# PowerSupply1.net
KiCad netlist of a schematic drawn in Altium Designer
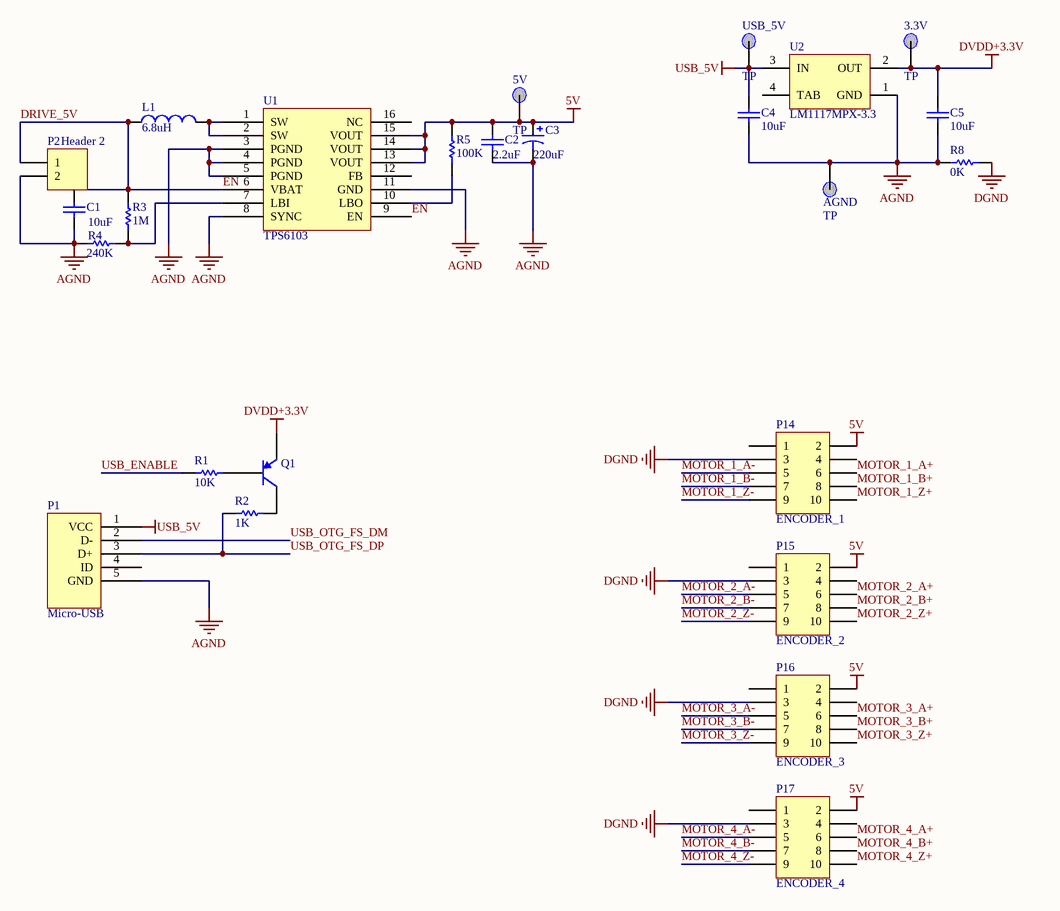
[diagram p0: PowerSupply1.SchDoc]

(export (version "E")
  (design (tool "Eeschema 10.0.6"))
  (components
    (comp (ref "3.3V") (value "TP") (footprint "TestPort") (libsource (lib "CTs_FYF") (part "TestPoint")))
    (comp (ref "5V") (value "TP") (footprint "TestPort") (libsource (lib "CTs_FYF") (part "TestPoint")))
    (comp (ref "AGND") (value "TP") (footprint "TestPort") (libsource (lib "") (part "TestPoint_1")))
    (comp (ref "C1")
      (value "10uF")
      (footprint "1608[0603]")
      (description "Capacitor")
      (fields (field (name "PUBLISHER") "Altium Limited"))
      (libsource (lib "Miscellaneous Devices") (part "Cap"))
    )
    (comp (ref "C2")
      (value "2.2uF")
      (footprint "1608[0603]")
      (description "Capacitor")
      (fields (field (name "PUBLISHER") "Altium Limited"))
      (libsource (lib "Miscellaneous Devices") (part "Cap"))
    )
    (comp (ref "C3")
      (value "220uF")
      (footprint "6TPF220M5L")
      (description "Polarized Capacitor (Radial)")
      (fields (field (name "PUBLISHER") "Altium Limited"))
      (libsource (lib "Miscellaneous Devices") (part "Cap Pol1"))
    )
    (comp (ref "C4")
      (value "10uF")
      (footprint "1608[0603]")
      (description "Capacitor")
      (fields (field (name "PUBLISHER") "Altium Limited"))
      (libsource (lib "Miscellaneous Devices") (part "Cap"))
    )
    (comp (ref "C5")
      (value "10uF")
      (footprint "1608[0603]")
      (description "Capacitor")
      (fields (field (name "PUBLISHER") "Altium Limited"))
      (libsource (lib "Miscellaneous Devices") (part "Cap"))
    )
    (comp (ref "L1")
      (value "6.8uH")
      (footprint "B82464G4682M")
      (description "Inductor")
      (fields (field (name "PUBLISHER") "Altium Limited"))
      (libsource (lib "Miscellaneous Devices") (part "Inductor"))
    )
    (comp (ref "P1")
      (value "Micro-USB")
      (footprint "Micro-USB")
      (libsource (lib "CTs_FYF") (part "Micro-USB"))
    )
    (comp (ref "P2")
      (value "Header 2")
      (footprint "HDR1X2")
      (description "Header, 2-Pin")
      (fields (field (name "PUBLISHER") "Altium Limited"))
      (libsource (lib "Miscellaneous Connectors") (part "Header 2"))
    )
    (comp (ref "P14")
      (value "ENCODER_1")
      (footprint "MHDR2X5")
      (description "Header, 5-Pin, Dual row")
      (fields (field (name "PUBLISHER") "Altium Limited"))
      (libsource (lib "Miscellaneous Connectors") (part "Header 5X2"))
    )
    (comp (ref "P15")
      (value "ENCODER_2")
      (footprint "MHDR2X5")
      (description "Header, 5-Pin, Dual row")
      (fields (field (name "PUBLISHER") "Altium Limited"))
      (libsource (lib "Miscellaneous Connectors") (part "Header 5X2"))
    )
    (comp (ref "P16")
      (value "ENCODER_3")
      (footprint "MHDR2X5")
      (description "Header, 5-Pin, Dual row")
      (fields (field (name "PUBLISHER") "Altium Limited"))
      (libsource (lib "Miscellaneous Connectors") (part "Header 5X2"))
    )
    (comp (ref "P17")
      (value "ENCODER_4")
      (footprint "MHDR2X5")
      (description "Header, 5-Pin, Dual row")
      (fields (field (name "PUBLISHER") "Altium Limited"))
      (libsource (lib "Miscellaneous Connectors") (part "Header 5X2"))
    )
    (comp (ref "Q1")
      (value "PNP")
      (footprint "SOT-23B_N")
      (description "PNP Bipolar Transistor")
      (fields (field (name "PUBLISHER") "Altium Limited"))
      (libsource (lib "Miscellaneous Devices") (part "PNP"))
    )
    (comp (ref "R1")
      (value "10K")
      (footprint "J1-0603")
      (description "Resistor")
      (fields (field (name "PUBLISHER") "Altium Limited"))
      (libsource (lib "Miscellaneous Devices") (part "Res1"))
    )
    (comp (ref "R2")
      (value "1K")
      (footprint "RES[0402]")
      (description "Resistor")
      (fields (field (name "PUBLISHER") "Altium Limited"))
      (libsource (lib "Miscellaneous Devices") (part "Res1"))
    )
    (comp (ref "R3")
      (value "1M")
      (footprint "J1-0603")
      (description "Resistor")
      (fields (field (name "PUBLISHER") "Altium Limited"))
      (libsource (lib "Miscellaneous Devices") (part "Res1"))
    )
    (comp (ref "R4")
      (value "240K")
      (footprint "J1-0603")
      (description "Resistor")
      (fields (field (name "PUBLISHER") "Altium Limited"))
      (libsource (lib "Miscellaneous Devices") (part "Res1"))
    )
    (comp (ref "R5")
      (value "100K")
      (footprint "J1-0603")
      (description "Resistor")
      (fields (field (name "PUBLISHER") "Altium Limited"))
      (libsource (lib "Miscellaneous Devices") (part "Res1"))
    )
    (comp (ref "R8")
      (value "0K")
      (footprint "J1-0603")
      (description "Resistor")
      (fields (field (name "PUBLISHER") "Altium Limited"))
      (libsource (lib "Miscellaneous Devices") (part "Res1"))
    )
    (comp (ref "U1") (value "TPS6103") (footprint "TI_PWP_G16") (libsource (lib "CTs_FYF") (part "TPS6103")))
    (comp (ref "U2")
      (value "LM1117MPX-3.3")
      (footprint "SOT230-4N")
      (description "800mA Low-Dropout Linear Regulator, 4-pin SOT-223")
      (fields
        (field (name "MANUFACTURER") "National Semiconductor")
        (field (name "PUBLISHER") "Altium Limited")
      )
      (libsource (lib "NSC LDO") (part "LM1117MPX-3.3"))
    )
    (comp (ref "USB_5V") (value "TP") (footprint "TestPort") (libsource (lib "CTs_FYF") (part "TestPoint")))
  )
  (nets
    (net (code "1") (name "/DRIVE_5V") (class "Default")
      (node (ref "C1") (pin "2") (pinfunction "2_2") (pintype "passive"))
      (node (ref "L1") (pin "1") (pinfunction "1_1") (pintype "passive"))
      (node (ref "P2") (pin "1") (pinfunction "1_1") (pintype "passive"))
      (node (ref "R3") (pin "2") (pinfunction "2_2") (pintype "passive"))
      (node (ref "U1") (pin "6") (pinfunction "VBAT_6") (pintype "passive"))
      (node (ref "U1") (pin "9") (pinfunction "EN_9") (pintype "passive"))
    )
    (net (code "2") (name "/MOTOR_1_A+") (class "Default")
      (node (ref "P14") (pin "6") (pinfunction "6_6") (pintype "passive"))
    )
    (net (code "3") (name "/MOTOR_1_A-") (class "Default")
      (node (ref "P14") (pin "5") (pinfunction "5_5") (pintype "passive"))
    )
    (net (code "4") (name "/MOTOR_1_B+") (class "Default")
      (node (ref "P14") (pin "8") (pinfunction "8_8") (pintype "passive"))
    )
    (net (code "5") (name "/MOTOR_1_B-") (class "Default")
      (node (ref "P14") (pin "7") (pinfunction "7_7") (pintype "passive"))
    )
    (net (code "6") (name "/MOTOR_1_Z+") (class "Default")
      (node (ref "P14") (pin "10") (pinfunction "10_10") (pintype "passive"))
    )
    (net (code "7") (name "/MOTOR_1_Z-") (class "Default")
      (node (ref "P14") (pin "9") (pinfunction "9_9") (pintype "passive"))
    )
    (net (code "8") (name "/MOTOR_2_A+") (class "Default")
      (node (ref "P15") (pin "6") (pinfunction "6_6") (pintype "passive"))
    )
    (net (code "9") (name "/MOTOR_2_A-") (class "Default")
      (node (ref "P15") (pin "5") (pinfunction "5_5") (pintype "passive"))
    )
    (net (code "10") (name "/MOTOR_2_B+") (class "Default")
      (node (ref "P15") (pin "8") (pinfunction "8_8") (pintype "passive"))
    )
    (net (code "11") (name "/MOTOR_2_B-") (class "Default")
      (node (ref "P15") (pin "7") (pinfunction "7_7") (pintype "passive"))
    )
    (net (code "12") (name "/MOTOR_2_Z+") (class "Default")
      (node (ref "P15") (pin "10") (pinfunction "10_10") (pintype "passive"))
    )
    (net (code "13") (name "/MOTOR_2_Z-") (class "Default")
      (node (ref "P15") (pin "9") (pinfunction "9_9") (pintype "passive"))
    )
    (net (code "14") (name "/MOTOR_3_A+") (class "Default")
      (node (ref "P16") (pin "6") (pinfunction "6_6") (pintype "passive"))
    )
    (net (code "15") (name "/MOTOR_3_A-") (class "Default")
      (node (ref "P16") (pin "5") (pinfunction "5_5") (pintype "passive"))
    )
    (net (code "16") (name "/MOTOR_3_B+") (class "Default")
      (node (ref "P16") (pin "8") (pinfunction "8_8") (pintype "passive"))
    )
    (net (code "17") (name "/MOTOR_3_B-") (class "Default")
      (node (ref "P16") (pin "7") (pinfunction "7_7") (pintype "passive"))
    )
    (net (code "18") (name "/MOTOR_3_Z+") (class "Default")
      (node (ref "P16") (pin "10") (pinfunction "10_10") (pintype "passive"))
    )
    (net (code "19") (name "/MOTOR_3_Z-") (class "Default")
      (node (ref "P16") (pin "9") (pinfunction "9_9") (pintype "passive"))
    )
    (net (code "20") (name "/MOTOR_4_A+") (class "Default")
      (node (ref "P17") (pin "6") (pinfunction "6_6") (pintype "passive"))
    )
    (net (code "21") (name "/MOTOR_4_A-") (class "Default")
      (node (ref "P17") (pin "5") (pinfunction "5_5") (pintype "passive"))
    )
    (net (code "22") (name "/MOTOR_4_B+") (class "Default")
      (node (ref "P17") (pin "8") (pinfunction "8_8") (pintype "passive"))
    )
    (net (code "23") (name "/MOTOR_4_B-") (class "Default")
      (node (ref "P17") (pin "7") (pinfunction "7_7") (pintype "passive"))
    )
    (net (code "24") (name "/MOTOR_4_Z+") (class "Default")
      (node (ref "P17") (pin "10") (pinfunction "10_10") (pintype "passive"))
    )
    (net (code "25") (name "/MOTOR_4_Z-") (class "Default")
      (node (ref "P17") (pin "9") (pinfunction "9_9") (pintype "passive"))
    )
    (net (code "26") (name "/USB_ENABLE") (class "Default")
      (node (ref "R1") (pin "1") (pinfunction "1_1") (pintype "passive"))
    )
    (net (code "27") (name "/USB_OTG_FS_DM") (class "Default")
      (node (ref "P1") (pin "2") (pinfunction "D-_2") (pintype "passive"))
    )
    (net (code "28") (name "/USB_OTG_FS_DP") (class "Default")
      (node (ref "P1") (pin "3") (pinfunction "D+_3") (pintype "passive"))
      (node (ref "R2") (pin "2") (pinfunction "2_2") (pintype "passive"))
    )
    (net (code "29") (name "5V") (class "Default")
      (node (ref "5V") (pin "0") (pinfunction "0_0") (pintype "passive"))
      (node (ref "C2") (pin "2") (pinfunction "2_2") (pintype "passive"))
      (node (ref "C3") (pin "1") (pinfunction "1_1") (pintype "passive"))
      (node (ref "P14") (pin "2") (pinfunction "2_2") (pintype "passive"))
      (node (ref "P15") (pin "2") (pinfunction "2_2") (pintype "passive"))
      (node (ref "P16") (pin "2") (pinfunction "2_2") (pintype "passive"))
      (node (ref "P17") (pin "2") (pinfunction "2_2") (pintype "passive"))
      (node (ref "R5") (pin "2") (pinfunction "2_2") (pintype "passive"))
      (node (ref "U1") (pin "13") (pinfunction "VOUT_13") (pintype "passive"))
      (node (ref "U1") (pin "14") (pinfunction "VOUT_14") (pintype "passive"))
      (node (ref "U1") (pin "15") (pinfunction "VOUT_15") (pintype "passive"))
    )
    (net (code "30") (name "AGND") (class "Default")
      (node (ref "AGND") (pin "0") (pinfunction "0_0") (pintype "passive"))
      (node (ref "C1") (pin "1") (pinfunction "1_1") (pintype "passive"))
      (node (ref "C2") (pin "1") (pinfunction "1_1") (pintype "passive"))
      (node (ref "C3") (pin "2") (pinfunction "2_2") (pintype "passive"))
      (node (ref "C4") (pin "2") (pinfunction "2_2") (pintype "passive"))
      (node (ref "C5") (pin "2") (pinfunction "2_2") (pintype "passive"))
      (node (ref "P1") (pin "5") (pinfunction "GND_5") (pintype "passive"))
      (node (ref "P2") (pin "2") (pinfunction "2_2") (pintype "passive"))
      (node (ref "R4") (pin "1") (pinfunction "1_1") (pintype "passive"))
      (node (ref "R8") (pin "1") (pinfunction "1_1") (pintype "passive"))
      (node (ref "U1") (pin "11") (pinfunction "GND_11") (pintype "passive"))
      (node (ref "U1") (pin "3") (pinfunction "PGND_3") (pintype "passive"))
      (node (ref "U1") (pin "4") (pinfunction "PGND_4") (pintype "passive"))
      (node (ref "U1") (pin "5") (pinfunction "PGND_5") (pintype "passive"))
      (node (ref "U1") (pin "8") (pinfunction "SYNC_8") (pintype "passive"))
      (node (ref "U2") (pin "1") (pinfunction "GND_1") (pintype "power_in"))
    )
    (net (code "31") (name "DGND") (class "Default")
      (node (ref "P14") (pin "3") (pinfunction "3_3") (pintype "passive"))
      (node (ref "P15") (pin "3") (pinfunction "3_3") (pintype "passive"))
      (node (ref "P16") (pin "3") (pinfunction "3_3") (pintype "passive"))
      (node (ref "P17") (pin "3") (pinfunction "3_3") (pintype "passive"))
      (node (ref "R8") (pin "2") (pinfunction "2_2") (pintype "passive"))
    )
    (net (code "32") (name "DVDD+3.3V") (class "Default")
      (node (ref "3.3V") (pin "0") (pinfunction "0_0") (pintype "passive"))
      (node (ref "C5") (pin "1") (pinfunction "1_1") (pintype "passive"))
      (node (ref "Q1") (pin "3") (pinfunction "E_3") (pintype "passive"))
      (node (ref "U2") (pin "2") (pinfunction "OUT_2") (pintype "power_in"))
    )
    (net (code "33") (name "Net-(L1-Pad2)") (class "Default")
      (node (ref "L1") (pin "2") (pinfunction "2_2") (pintype "passive"))
      (node (ref "U1") (pin "1") (pinfunction "SW_1") (pintype "passive"))
      (node (ref "U1") (pin "2") (pinfunction "SW_2") (pintype "passive"))
    )
    (net (code "34") (name "Net-(Q1-B)") (class "Default")
      (node (ref "Q1") (pin "2") (pinfunction "B_2") (pintype "passive"))
      (node (ref "R1") (pin "2") (pinfunction "2_2") (pintype "passive"))
    )
    (net (code "35") (name "Net-(Q1-C)") (class "Default")
      (node (ref "Q1") (pin "1") (pinfunction "C_1") (pintype "passive"))
      (node (ref "R2") (pin "1") (pinfunction "1_1") (pintype "passive"))
    )
    (net (code "36") (name "Net-(U1-LBI)") (class "Default")
      (node (ref "R3") (pin "1") (pinfunction "1_1") (pintype "passive"))
      (node (ref "R4") (pin "2") (pinfunction "2_2") (pintype "passive"))
      (node (ref "U1") (pin "7") (pinfunction "LBI_7") (pintype "passive"))
    )
    (net (code "37") (name "Net-(U1-LBO)") (class "Default")
      (node (ref "R5") (pin "1") (pinfunction "1_1") (pintype "passive"))
      (node (ref "U1") (pin "10") (pinfunction "LBO_10") (pintype "passive"))
    )
    (net (code "38") (name "USB_5V") (class "Default")
      (node (ref "C4") (pin "1") (pinfunction "1_1") (pintype "passive"))
      (node (ref "P1") (pin "1") (pinfunction "VCC_1") (pintype "passive"))
      (node (ref "U2") (pin "3") (pinfunction "IN_3") (pintype "power_in"))
      (node (ref "USB_5V") (pin "0") (pinfunction "0_0") (pintype "passive"))
    )
    (net (code "39") (name "unconnected-(P1-ID-Pad4)") (class "Default")
      (node (ref "P1") (pin "4") (pinfunction "ID_4") (pintype "passive"))
    )
    (net (code "40") (name "unconnected-(P14-Pad1)") (class "Default")
      (node (ref "P14") (pin "1") (pinfunction "1_1") (pintype "passive"))
    )
    (net (code "41") (name "unconnected-(P14-Pad4)") (class "Default")
      (node (ref "P14") (pin "4") (pinfunction "4_4") (pintype "passive"))
    )
    (net (code "42") (name "unconnected-(P15-Pad1)") (class "Default")
      (node (ref "P15") (pin "1") (pinfunction "1_1") (pintype "passive"))
    )
    (net (code "43") (name "unconnected-(P15-Pad4)") (class "Default")
      (node (ref "P15") (pin "4") (pinfunction "4_4") (pintype "passive"))
    )
    (net (code "44") (name "unconnected-(P16-Pad1)") (class "Default")
      (node (ref "P16") (pin "1") (pinfunction "1_1") (pintype "passive"))
    )
    (net (code "45") (name "unconnected-(P16-Pad4)") (class "Default")
      (node (ref "P16") (pin "4") (pinfunction "4_4") (pintype "passive"))
    )
    (net (code "46") (name "unconnected-(P17-Pad1)") (class "Default")
      (node (ref "P17") (pin "1") (pinfunction "1_1") (pintype "passive"))
    )
    (net (code "47") (name "unconnected-(P17-Pad4)") (class "Default")
      (node (ref "P17") (pin "4") (pinfunction "4_4") (pintype "passive"))
    )
    (net (code "48") (name "unconnected-(U1-FB-Pad12)") (class "Default")
      (node (ref "U1") (pin "12") (pinfunction "FB_12") (pintype "passive"))
    )
    (net (code "49") (name "unconnected-(U1-NC-Pad16)") (class "Default")
      (node (ref "U1") (pin "16") (pinfunction "NC_16") (pintype "passive"))
    )
    (net (code "50") (name "unconnected-(U2-TAB-Pad4)") (class "Default")
      (node (ref "U2") (pin "4") (pinfunction "TAB_4") (pintype "power_in"))
    )
  )
)
